# MediaControllerSchem.net
KiCad netlist of a schematic drawn in Altium Designer
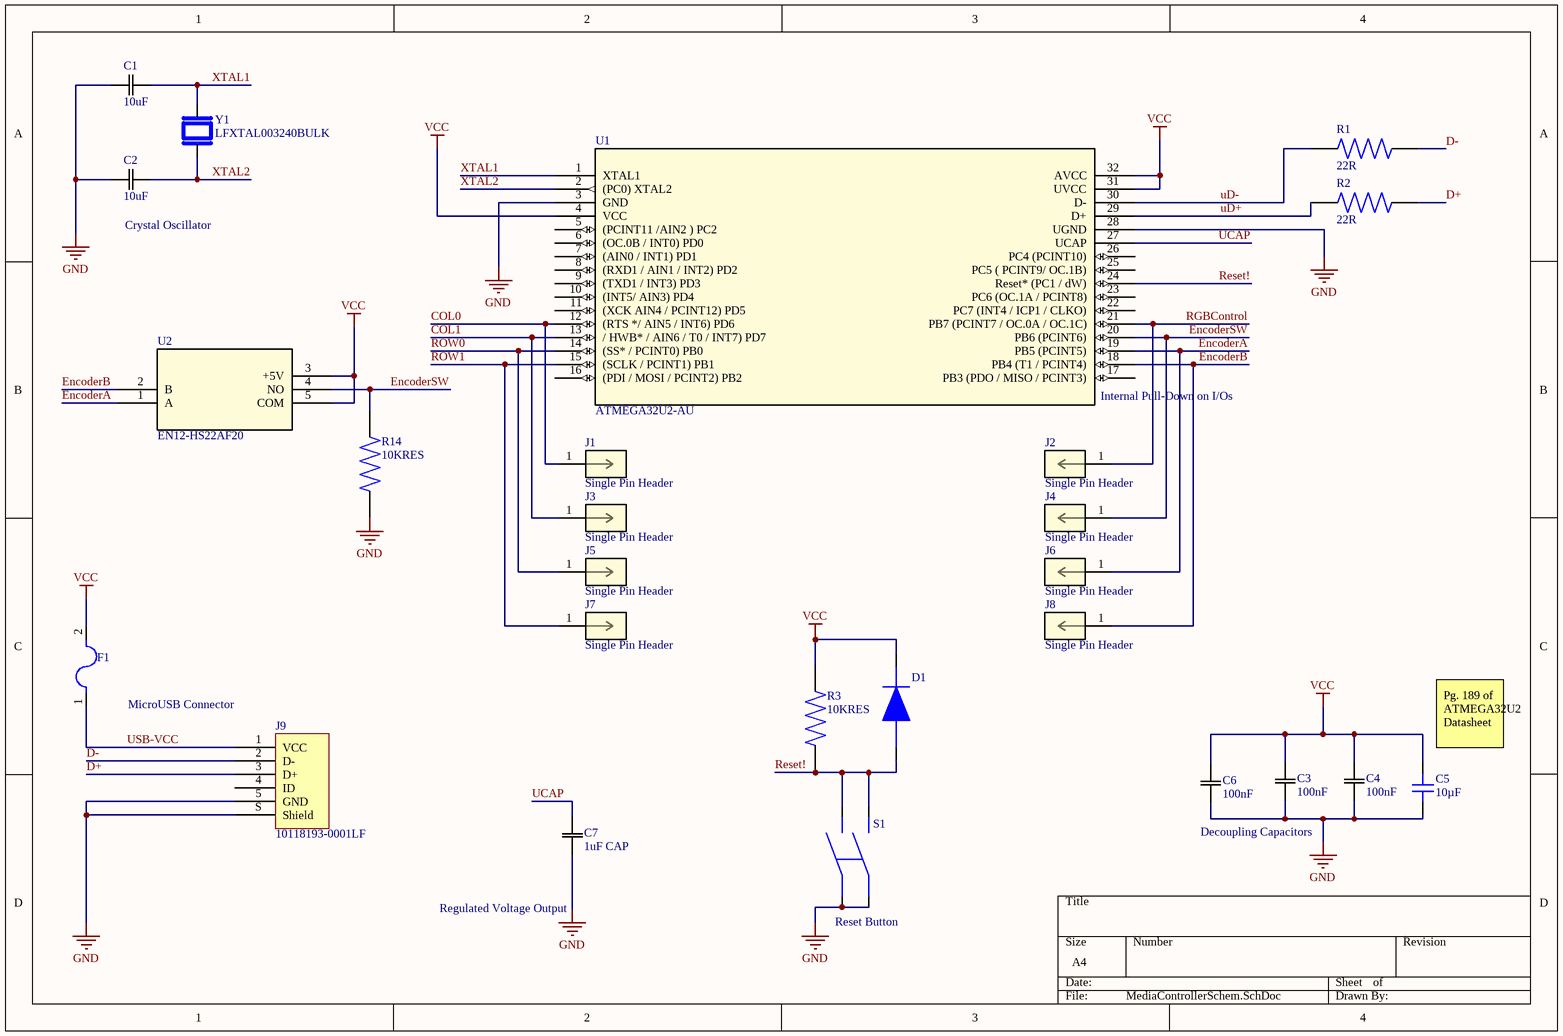
[diagram p0: MediaControllerSchem.SchDoc]

(export (version "E")
  (design (tool "Eeschema 10.0.6"))
  (components
    (comp (ref "C1")
      (value "10uF")
      (footprint "CAPC17090_87N_KEM-L")
      (description "Multilayer Ceramic Capacitors MLCC - SMD/SMT 50V 10pF C0G 0603 5%")
      (fields
        (field (name "MANUFACTURER_PART_NUMBER") "CBR06C100J5GAC")
        (field (name "COPYRIGHT") "Copyright (C) 2021 Accelerated Designs. All rights reserved")
      )
      (libsource (lib "MediaControllerSchLib") (part "10pFCap"))
    )
    (comp (ref "C2")
      (value "10uF")
      (footprint "CAPC17090_87N_KEM-L")
      (description "Multilayer Ceramic Capacitors MLCC - SMD/SMT 50V 10pF C0G 0603 5%")
      (fields
        (field (name "MANUFACTURER_PART_NUMBER") "CBR06C100J5GAC")
        (field (name "COPYRIGHT") "Copyright (C) 2021 Accelerated Designs. All rights reserved")
      )
      (libsource (lib "MediaControllerSchLib") (part "10pFCap"))
    )
    (comp (ref "C3")
      (value "100nF")
      (footprint "CAPC0603_87N_KEM-M")
      (description "CAP CER 10000PF 50V U2J 0603")
      (fields
        (field (name "MANUFACTURER") "KEMET")
        (field (name "MANUFACTURER PART NUMBER") "C0603C103J5JACTU")
      )
      (libsource (lib "MediaControllerSchLib") (part "C0603C103J5JACTU"))
    )
    (comp (ref "C4")
      (value "100nF")
      (footprint "CAPC0603_87N_KEM-M")
      (description "CAP CER 10000PF 50V U2J 0603")
      (fields
        (field (name "MANUFACTURER") "KEMET")
        (field (name "MANUFACTURER PART NUMBER") "C0603C103J5JACTU")
      )
      (libsource (lib "MediaControllerSchLib") (part "C0603C103J5JACTU"))
    )
    (comp (ref "C5")
      (value "10µF")
      (footprint "CAP 0603_1608")
      (description "CAP CER 10UF 25V X5R 0603")
      (fields
        (field (name "PART NUMBER") "GRM188R61E106MA73D")
        (field (name "MANUFACTURER") "Murata Electronics")
      )
      (libsource (lib "Celestial Altium Library - altium_library") (part "Capacitor"))
    )
    (comp (ref "C6")
      (value "100nF")
      (footprint "CAPC0603_87N_KEM-M")
      (description "CAP CER 10000PF 50V U2J 0603")
      (fields
        (field (name "MANUFACTURER") "KEMET")
        (field (name "MANUFACTURER PART NUMBER") "C0603C103J5JACTU")
      )
      (libsource (lib "MediaControllerSchLib") (part "C0603C103J5JACTU"))
    )
    (comp (ref "C7")
      (value "1uF CAP")
      (footprint "1UFCAP-M")
      (fields
        (field (name "MANUFACTURER") "KEMET")
        (field (name "MANUFACTURER PART NUMBER") "C0603C105K8PACTU")
        (field (name "TOLERANCE") "10%")
      )
      (libsource (lib "MediaControllerSchLib") (part "1uFCap"))
    )
    (comp (ref "D1")
      (value "RectifierDiode")
      (footprint "DO-219AB_VIS-M")
      (description "VISHAY - ES07D-GS08 - Fast / Ultrafast Diode, 200 V, 1.2 A, Single, 980 mV, 25 ns, 30 A")
      (fields (field (name "MANUFACTURER") "Vishay") (field (name "MANUFACTURER PART NUMBER") "ES07D-GS08"))
      (libsource (lib "MediaControllerSchLib") (part "ES07D-GS08"))
    )
    (comp (ref "F1")
      (value "500mAFuse")
      (footprint "FUSC6125X279N")
      (description "Fuse Chip Fast Acting 0.5A 350V Solder Pad SMD 2410 Ceramic T/R")
      (fields (field (name "MANUFACTURER") "Bel") (field (name "MANUFACTURER PART NUMBER") "0679H0500-05"))
      (libsource (lib "MediaControllerSchLib") (part "Fuse"))
    )
    (comp (ref "J1")
      (value "Single Pin Header")
      (footprint "CON1_1X1_TU_TSW")
      (description "Samtec TSW, 1 Way, 1 Row, Straight PCB Header")
      (fields
        (field (name "MANUFACTURER") "Samtec")
        (field (name "MANUFACTURER PART NUMBER") "TSW-101-07-F-S")
      )
      (libsource (lib "MediaControllerSchLib") (part "TSW-101-07-F-S"))
    )
    (comp (ref "J2")
      (value "Single Pin Header")
      (footprint "CON1_1X1_TU_TSW")
      (description "Samtec TSW, 1 Way, 1 Row, Straight PCB Header")
      (fields
        (field (name "MANUFACTURER") "Samtec")
        (field (name "MANUFACTURER PART NUMBER") "TSW-101-07-F-S")
      )
      (libsource (lib "") (part "TSW-101-07-F-S_1"))
    )
    (comp (ref "J3")
      (value "Single Pin Header")
      (footprint "CON1_1X1_TU_TSW")
      (description "Samtec TSW, 1 Way, 1 Row, Straight PCB Header")
      (fields
        (field (name "MANUFACTURER") "Samtec")
        (field (name "MANUFACTURER PART NUMBER") "TSW-101-07-F-S")
      )
      (libsource (lib "MediaControllerSchLib") (part "TSW-101-07-F-S"))
    )
    (comp (ref "J4")
      (value "Single Pin Header")
      (footprint "CON1_1X1_TU_TSW")
      (description "Samtec TSW, 1 Way, 1 Row, Straight PCB Header")
      (fields
        (field (name "MANUFACTURER") "Samtec")
        (field (name "MANUFACTURER PART NUMBER") "TSW-101-07-F-S")
      )
      (libsource (lib "") (part "TSW-101-07-F-S_1"))
    )
    (comp (ref "J5")
      (value "Single Pin Header")
      (footprint "CON1_1X1_TU_TSW")
      (description "Samtec TSW, 1 Way, 1 Row, Straight PCB Header")
      (fields
        (field (name "MANUFACTURER") "Samtec")
        (field (name "MANUFACTURER PART NUMBER") "TSW-101-07-F-S")
      )
      (libsource (lib "MediaControllerSchLib") (part "TSW-101-07-F-S"))
    )
    (comp (ref "J6")
      (value "Single Pin Header")
      (footprint "CON1_1X1_TU_TSW")
      (description "Samtec TSW, 1 Way, 1 Row, Straight PCB Header")
      (fields
        (field (name "MANUFACTURER") "Samtec")
        (field (name "MANUFACTURER PART NUMBER") "TSW-101-07-F-S")
      )
      (libsource (lib "") (part "TSW-101-07-F-S_1"))
    )
    (comp (ref "J7")
      (value "Single Pin Header")
      (footprint "CON1_1X1_TU_TSW")
      (description "Samtec TSW, 1 Way, 1 Row, Straight PCB Header")
      (fields
        (field (name "MANUFACTURER") "Samtec")
        (field (name "MANUFACTURER PART NUMBER") "TSW-101-07-F-S")
      )
      (libsource (lib "MediaControllerSchLib") (part "TSW-101-07-F-S"))
    )
    (comp (ref "J8")
      (value "Single Pin Header")
      (footprint "CON1_1X1_TU_TSW")
      (description "Samtec TSW, 1 Way, 1 Row, Straight PCB Header")
      (fields
        (field (name "MANUFACTURER") "Samtec")
        (field (name "MANUFACTURER PART NUMBER") "TSW-101-07-F-S")
      )
      (libsource (lib "") (part "TSW-101-07-F-S_1"))
    )
    (comp (ref "J9")
      (value "10118193-0001LF")
      (footprint "FCI USB 10118193-0001LF")
      (description "CONN RCPT USB2.0 MICRO B SMD R/A")
      (fields (field (name "MANUFACTURER") "Amphenol ICC (FCI)"))
      (libsource (lib "Celestial Altium Library - altium_library") (part "USB 2.0 Type B Micro"))
    )
    (comp (ref "R1")
      (value "22R")
      (footprint "RES0603_22OHM")
      (description "RES SMD 22 OHM 5% 1/4W 0603")
      (fields
        (field (name "MANUFACTURER") "Vishay Dale")
        (field (name "MANUFACTURER PART NUMBER") "RCS060322R0JNEA")
      )
      (libsource (lib "MediaControllerSchLib") (part "22Res"))
    )
    (comp (ref "R2")
      (value "22R")
      (footprint "RES0603_22OHM")
      (description "RES SMD 22 OHM 5% 1/4W 0603")
      (fields
        (field (name "MANUFACTURER") "Vishay Dale")
        (field (name "MANUFACTURER PART NUMBER") "RCS060322R0JNEA")
      )
      (libsource (lib "MediaControllerSchLib") (part "22Res"))
    )
    (comp (ref "R3")
      (value "10KRES")
      (footprint "RES0603")
      (description "Res Thick Film 0603 10K Ohm 5% 1/10W ±200ppm/°C Molded SMD")
      (fields
        (field (name "MANUFACTURER") "Vishay Dale")
        (field (name "MANUFACTURER PART NUMBER") "RCG060310K0JNEA")
      )
      (libsource (lib "MediaControllerSchLib") (part "10kRes"))
    )
    (comp (ref "R14")
      (value "10KRES")
      (footprint "RES0603")
      (description "Res Thick Film 0603 10K Ohm 5% 1/10W ±200ppm/°C Molded SMD")
      (fields
        (field (name "MANUFACTURER") "Vishay Dale")
        (field (name "MANUFACTURER PART NUMBER") "RCG060310K0JNEA")
      )
      (libsource (lib "MediaControllerSchLib") (part "10kRes"))
    )
    (comp (ref "S1")
      (value "TacticalSwitch")
      (footprint "TACTILESWITCH")
      (description "E-SWITCH - TL3305AF160QG - TACTILE SW, SPST, 0.05A, 12VDC, SOLDER")
      (fields
        (field (name "MANUFACTURER") "E-Switch")
        (field (name "MANUFACTURER PART NUMBER") "TL3305AF160QG")
      )
      (libsource (lib "MediaControllerSchLib") (part "TacticalSwitch"))
    )
    (comp (ref "U1")
      (value "ATMEGA32U2-AU")
      (footprint "32A_ATM")
      (description "8-bit Microcontroller with 8/16/32K Bytes of ISP Flash and USB Controller")
      (fields (field (name "COPYRIGHT") "Copyright (C) 2021 Accelerated Designs. All rights reserved"))
      (libsource (lib "MediaControllerSchLib") (part "ATMEGA32U2-AU"))
    )
    (comp (ref "U2")
      (value "EN12-HS22AF20")
      (footprint "EN12-HS_TTE")
      (description "BI TECHNOLOGIES / TT ELECTRONICS         EN12-HS22AF20             INCREMENTAL ENCODER")
      (fields (field (name "MANUFACTURER") "TT BI"))
      (libsource (lib "MediaControllerSchLib") (part "EN12-HS22AF20"))
    )
    (comp (ref "Y1")
      (value "LFXTAL003240BULK")
      (footprint "LFXTAL003240BULK")
      (description "16MHz Â±30ppm Crystal 30pF 40 Ohms HC-49/US")
      (fields (field (name "MF") "IQD Frequency Products"))
      (libsource (lib "MediaControllerSchLib") (part "LFXTAL003240BULK"))
    )
  )
  (nets
    (net (code "1") (name "/COL0") (class "Default")
      (node (ref "J1") (pin "1") (pinfunction "1_1") (pintype "passive"))
      (node (ref "U1") (pin "12") (pinfunction "(RTS_*/_AIN5_/_INT6)_PD6_12") (pintype "bidirectional"))
    )
    (net (code "2") (name "/COL1") (class "Default")
      (node (ref "J3") (pin "1") (pinfunction "1_1") (pintype "passive"))
      (node (ref "U1") (pin "13") (pinfunction "/_HWB*_/_AIN6_/_T0_/_INT7)_PD7_13") (pintype "bidirectional"))
    )
    (net (code "3") (name "/D+") (class "Default")
      (node (ref "J9") (pin "3") (pinfunction "D+_3") (pintype "passive"))
      (node (ref "R2") (pin "2") (pinfunction "2_2") (pintype "passive"))
    )
    (net (code "4") (name "/D-") (class "Default")
      (node (ref "J9") (pin "2") (pinfunction "D-_2") (pintype "passive"))
      (node (ref "R1") (pin "2") (pinfunction "2_2") (pintype "passive"))
    )
    (net (code "5") (name "/EncoderA") (class "Default")
      (node (ref "J6") (pin "1") (pinfunction "1_1") (pintype "passive"))
      (node (ref "U1") (pin "19") (pinfunction "PB5_(PCINT5)_19") (pintype "bidirectional"))
      (node (ref "U2") (pin "1") (pinfunction "A_1") (pintype "passive"))
    )
    (net (code "6") (name "/EncoderB") (class "Default")
      (node (ref "J8") (pin "1") (pinfunction "1_1") (pintype "passive"))
      (node (ref "U1") (pin "18") (pinfunction "PB4_(T1_/_PCINT4)_18") (pintype "bidirectional"))
      (node (ref "U2") (pin "2") (pinfunction "B_2") (pintype "passive"))
    )
    (net (code "7") (name "/EncoderSW") (class "Default")
      (node (ref "J4") (pin "1") (pinfunction "1_1") (pintype "passive"))
      (node (ref "R14") (pin "2") (pinfunction "2_2") (pintype "passive"))
      (node (ref "U1") (pin "20") (pinfunction "PB6_(PCINT6)_20") (pintype "bidirectional"))
      (node (ref "U2") (pin "4") (pinfunction "NO_4") (pintype "passive"))
    )
    (net (code "8") (name "/RGBControl") (class "Default")
      (node (ref "J2") (pin "1") (pinfunction "1_1") (pintype "passive"))
      (node (ref "U1") (pin "21") (pinfunction "PB7_(PCINT7_/_OC.0A_/_OC.1C)_21") (pintype "bidirectional"))
    )
    (net (code "9") (name "/ROW0") (class "Default")
      (node (ref "J5") (pin "1") (pinfunction "1_1") (pintype "passive"))
      (node (ref "U1") (pin "14") (pinfunction "(SS*_/_PCINT0)_PB0_14") (pintype "bidirectional"))
    )
    (net (code "10") (name "/ROW1") (class "Default")
      (node (ref "J7") (pin "1") (pinfunction "1_1") (pintype "passive"))
      (node (ref "U1") (pin "15") (pinfunction "(SCLK_/_PCINT1)_PB1_15") (pintype "bidirectional"))
    )
    (net (code "11") (name "/Reset!") (class "Default")
      (node (ref "D1") (pin "1") (pinfunction "1_1") (pintype "passive"))
      (node (ref "R3") (pin "1") (pinfunction "1_1") (pintype "passive"))
      (node (ref "S1") (pin "3") (pinfunction "3_3") (pintype "passive"))
      (node (ref "S1") (pin "4") (pinfunction "4_4") (pintype "passive"))
      (node (ref "U1") (pin "24") (pinfunction "Reset*_(PC1_/_dW)_24") (pintype "bidirectional"))
    )
    (net (code "12") (name "/UCAP") (class "Default")
      (node (ref "C7") (pin "2") (pinfunction "2_2") (pintype "passive"))
      (node (ref "U1") (pin "27") (pinfunction "UCAP_27") (pintype "power_in"))
    )
    (net (code "13") (name "/USB-VCC") (class "Default")
      (node (ref "F1") (pin "1") (pinfunction "1_1") (pintype "passive"))
      (node (ref "J9") (pin "1") (pinfunction "VCC_1") (pintype "passive"))
    )
    (net (code "14") (name "/XTAL1") (class "Default")
      (node (ref "C1") (pin "2") (pinfunction "2_2") (pintype "passive"))
      (node (ref "U1") (pin "1") (pinfunction "XTAL1_1") (pintype "passive"))
      (node (ref "Y1") (pin "2") (pinfunction "2_2") (pintype "passive"))
    )
    (net (code "15") (name "/XTAL2") (class "Default")
      (node (ref "C2") (pin "2") (pinfunction "2_2") (pintype "passive"))
      (node (ref "U1") (pin "2") (pinfunction "(PC0)_XTAL2_2") (pintype "output"))
      (node (ref "Y1") (pin "1") (pinfunction "1_1") (pintype "passive"))
    )
    (net (code "16") (name "/uD+") (class "Default")
      (node (ref "R2") (pin "1") (pinfunction "1_1") (pintype "passive"))
      (node (ref "U1") (pin "29") (pinfunction "D+_29") (pintype "passive"))
    )
    (net (code "17") (name "/uD-") (class "Default")
      (node (ref "R1") (pin "1") (pinfunction "1_1") (pintype "passive"))
      (node (ref "U1") (pin "30") (pinfunction "D-_30") (pintype "passive"))
    )
    (net (code "18") (name "GND") (class "Default")
      (node (ref "C1") (pin "1") (pinfunction "1_1") (pintype "passive"))
      (node (ref "C2") (pin "1") (pinfunction "1_1") (pintype "passive"))
      (node (ref "C3") (pin "1") (pinfunction "1_1") (pintype "passive"))
      (node (ref "C4") (pin "1") (pinfunction "1_1") (pintype "passive"))
      (node (ref "C5") (pin "1") (pinfunction "1_1") (pintype "passive"))
      (node (ref "C6") (pin "1") (pinfunction "1_1") (pintype "passive"))
      (node (ref "C7") (pin "1") (pinfunction "1_1") (pintype "passive"))
      (node (ref "J9") (pin "5") (pinfunction "GND_5") (pintype "passive"))
      (node (ref "J9") (pin "S") (pinfunction "Shield_S") (pintype "passive"))
      (node (ref "R14") (pin "1") (pinfunction "1_1") (pintype "passive"))
      (node (ref "S1") (pin "1") (pinfunction "1_1") (pintype "passive"))
      (node (ref "S1") (pin "2") (pinfunction "2_2") (pintype "passive"))
      (node (ref "U1") (pin "28") (pinfunction "UGND_28") (pintype "power_in"))
      (node (ref "U1") (pin "3") (pinfunction "GND_3") (pintype "power_in"))
    )
    (net (code "19") (name "VCC") (class "Default")
      (node (ref "C3") (pin "2") (pinfunction "2_2") (pintype "passive"))
      (node (ref "C4") (pin "2") (pinfunction "2_2") (pintype "passive"))
      (node (ref "C5") (pin "2") (pinfunction "2_2") (pintype "passive"))
      (node (ref "C6") (pin "2") (pinfunction "2_2") (pintype "passive"))
      (node (ref "D1") (pin "2") (pinfunction "2_2") (pintype "passive"))
      (node (ref "F1") (pin "2") (pinfunction "2_2") (pintype "passive"))
      (node (ref "R3") (pin "2") (pinfunction "2_2") (pintype "passive"))
      (node (ref "U1") (pin "31") (pinfunction "UVCC_31") (pintype "power_in"))
      (node (ref "U1") (pin "32") (pinfunction "AVCC_32") (pintype "power_in"))
      (node (ref "U1") (pin "4") (pinfunction "VCC_4") (pintype "power_in"))
      (node (ref "U2") (pin "3") (pinfunction "+5V_3") (pintype "passive"))
      (node (ref "U2") (pin "5") (pinfunction "COM_5") (pintype "passive"))
    )
    (net (code "20") (name "unconnected-(J9-ID-Pad4)") (class "Default")
      (node (ref "J9") (pin "4") (pinfunction "ID_4") (pintype "passive"))
    )
    (net (code "21") (name "unconnected-(U1-(AIN0_{slash}_INT1)_PD1-Pad7)") (class "Default")
      (node (ref "U1") (pin "7") (pinfunction "(AIN0_/_INT1)_PD1_7") (pintype "bidirectional"))
    )
    (net (code "22") (name "unconnected-(U1-(INT5{slash}_AIN3)_PD4-Pad10)") (class "Default")
      (node (ref "U1") (pin "10") (pinfunction "(INT5/_AIN3)_PD4_10") (pintype "bidirectional"))
    )
    (net (code "23") (name "unconnected-(U1-(OC.0B_{slash}_INT0)_PD0-Pad6)") (class "Default")
      (node (ref "U1") (pin "6") (pinfunction "(OC.0B_/_INT0)_PD0_6") (pintype "bidirectional"))
    )
    (net (code "24") (name "unconnected-(U1-(PCINT11_{slash}AIN2_)_PC2-Pad5)") (class "Default")
      (node (ref "U1") (pin "5") (pinfunction "(PCINT11_/AIN2_)_PC2_5") (pintype "bidirectional"))
    )
    (net (code "25") (name "unconnected-(U1-(PDI_{slash}_MOSI_{slash}_PCINT2)_PB2-Pad16)") (class "Default")
      (node (ref "U1") (pin "16") (pinfunction "(PDI_/_MOSI_/_PCINT2)_PB2_16") (pintype "bidirectional"))
    )
    (net (code "26") (name "unconnected-(U1-(RXD1_{slash}_AIN1_{slash}_INT2)_PD2-Pad8)") (class "Default")
      (node (ref "U1") (pin "8") (pinfunction "(RXD1_/_AIN1_/_INT2)_PD2_8") (pintype "bidirectional"))
    )
    (net (code "27") (name "unconnected-(U1-(TXD1_{slash}_INT3)_PD3-Pad9)") (class "Default")
      (node (ref "U1") (pin "9") (pinfunction "(TXD1_/_INT3)_PD3_9") (pintype "bidirectional"))
    )
    (net (code "28") (name "unconnected-(U1-(XCK_AIN4_{slash}_PCINT12)_PD5-Pad11)") (class "Default")
      (node (ref "U1") (pin "11") (pinfunction "(XCK_AIN4_/_PCINT12)_PD5_11") (pintype "bidirectional"))
    )
    (net (code "29") (name "unconnected-(U1-PB3_(PDO_{slash}_MISO_{slash}_PCINT3)-Pad17)") (class "Default")
      (node (ref "U1") (pin "17") (pinfunction "PB3_(PDO_/_MISO_/_PCINT3)_17") (pintype "bidirectional"))
    )
    (net (code "30") (name "unconnected-(U1-PC4_(PCINT10)-Pad26)") (class "Default")
      (node (ref "U1") (pin "26") (pinfunction "PC4_(PCINT10)_26") (pintype "bidirectional"))
    )
    (net (code "31") (name "unconnected-(U1-PC5_(_PCINT9{slash}_OC.1B)-Pad25)") (class "Default")
      (node (ref "U1") (pin "25") (pinfunction "PC5_(_PCINT9/_OC.1B)_25") (pintype "bidirectional"))
    )
    (net (code "32") (name "unconnected-(U1-PC6_(OC.1A_{slash}_PCINT8)-Pad23)") (class "Default")
      (node (ref "U1") (pin "23") (pinfunction "PC6_(OC.1A_/_PCINT8)_23") (pintype "bidirectional"))
    )
    (net (code "33") (name "unconnected-(U1-PC7_(INT4_{slash}_ICP1_{slash}_CLKO)-Pad22)") (class "Default")
      (node (ref "U1") (pin "22") (pinfunction "PC7_(INT4_/_ICP1_/_CLKO)_22") (pintype "bidirectional"))
    )
  )
)
